# control_board.net
KiCad netlist of a schematic drawn in EAGLE
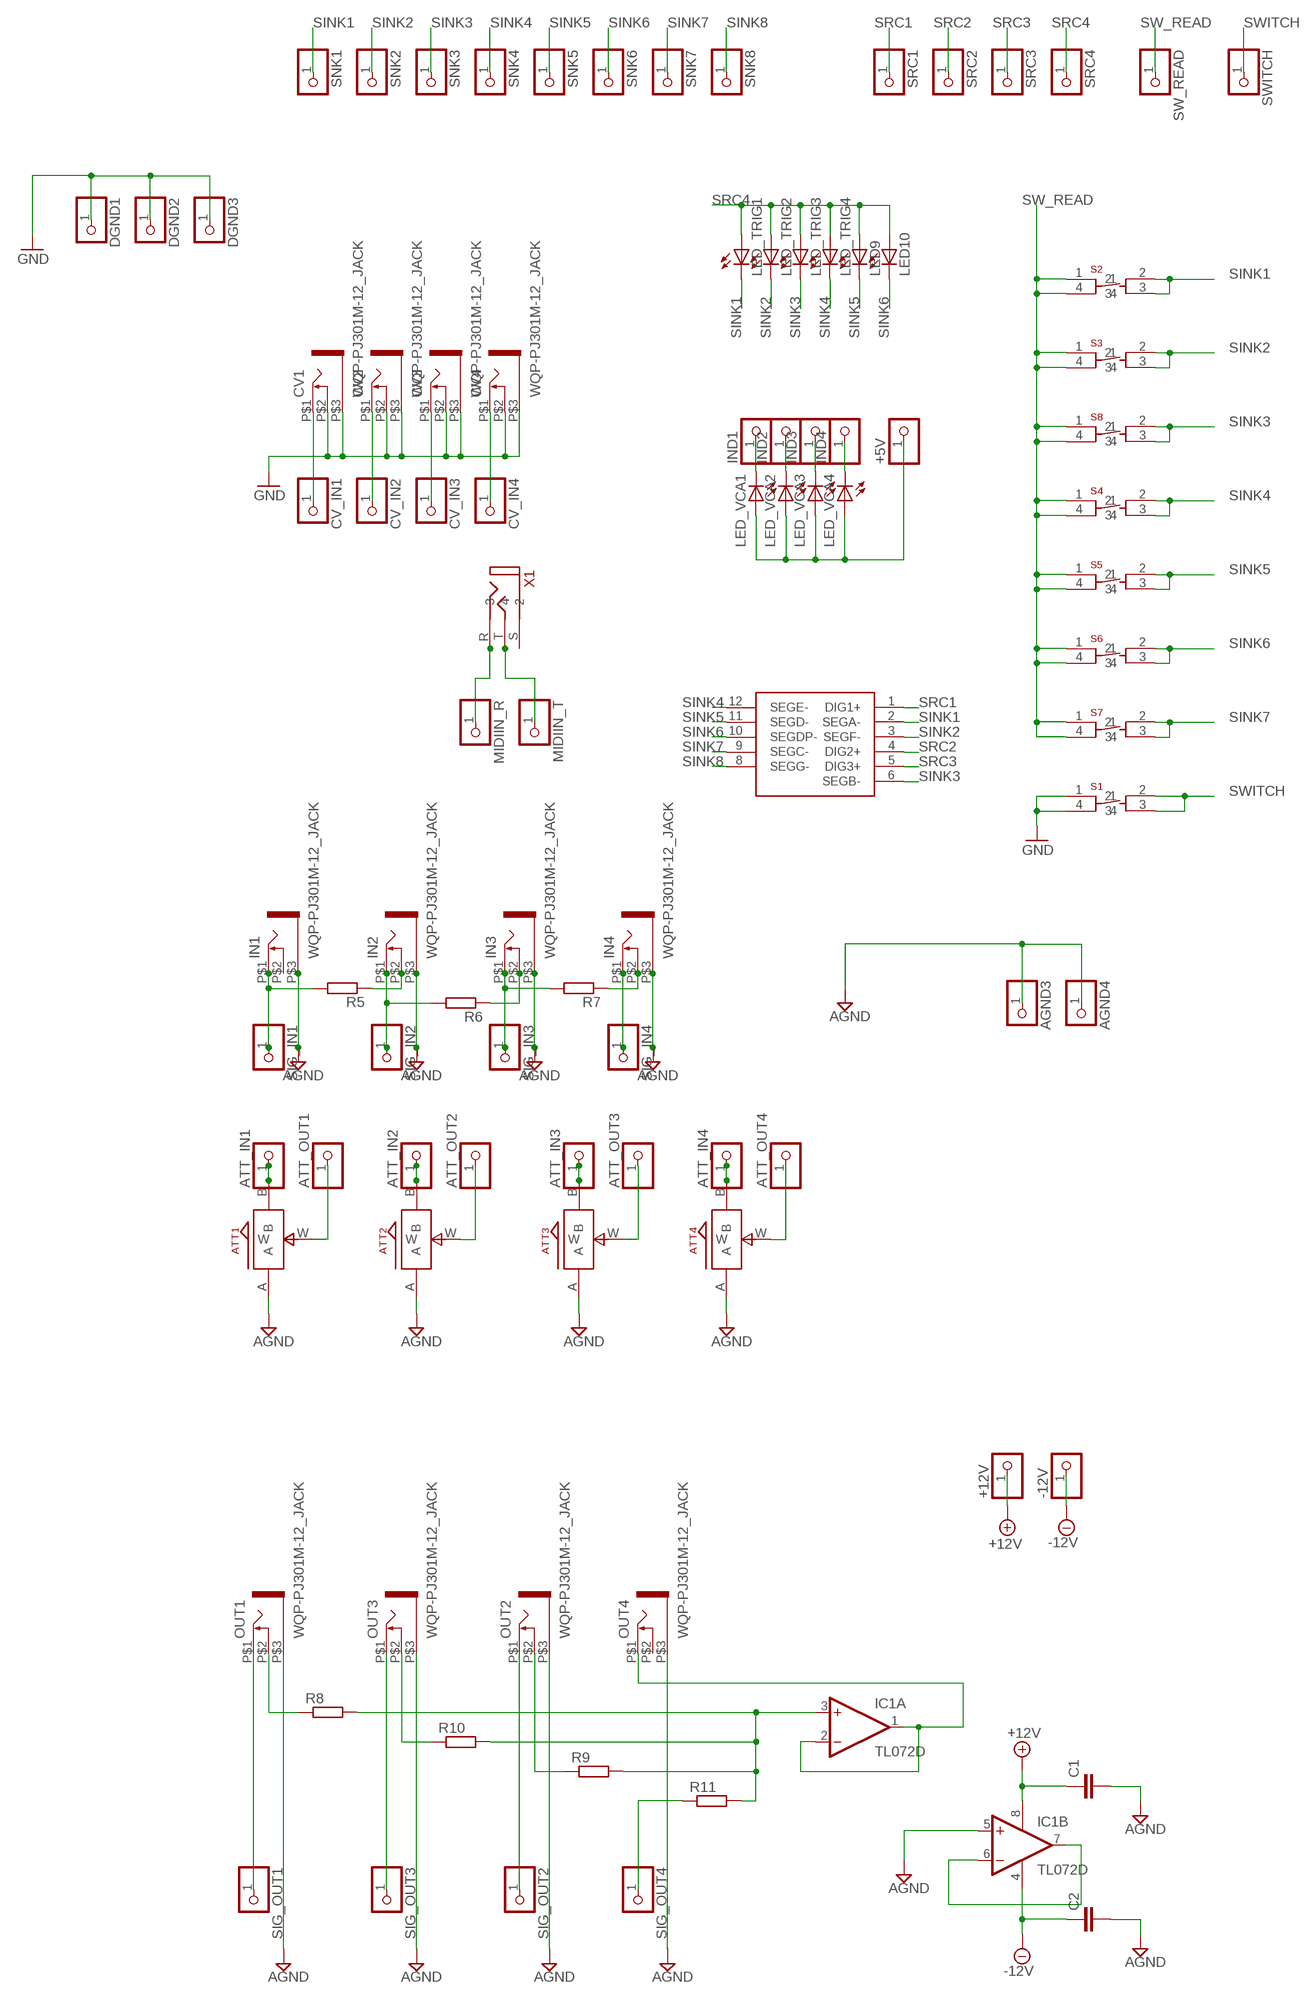
[diagram p0: schematic, sheet 1]

(export (version "E")
  (design (tool "Eeschema 10.0.6"))
  (components
    (comp (ref "+5V")
      (value "PINHD-1X1")
      (footprint "eagle-import:1X01")
      (libsource (lib "eagle-import") (part "PINHD-1X1"))
    )
    (comp (ref "+12V")
      (value "PINHD-1X1")
      (footprint "eagle-import:1X01")
      (libsource (lib "eagle-import") (part "PINHD-1X1"))
    )
    (comp (ref "-12V")
      (value "PINHD-1X1")
      (footprint "eagle-import:1X01")
      (libsource (lib "eagle-import") (part "PINHD-1X1"))
    )
    (comp (ref "AGND3")
      (value "PINHD-1X1")
      (footprint "eagle-import:1X01")
      (libsource (lib "eagle-import") (part "PINHD-1X1"))
    )
    (comp (ref "AGND4")
      (value "PINHD-1X1")
      (footprint "eagle-import:1X01")
      (libsource (lib "eagle-import") (part "PINHD-1X1"))
    )
    (comp (ref "ATT1")
      (value "ALPS_POT_SMALL")
      (footprint "eagle-import:SMALL_ALPS_POT")
      (libsource (lib "eagle-import") (part "ALPS_POT_SMALL"))
    )
    (comp (ref "ATT2")
      (value "ALPS_POT_SMALL")
      (footprint "eagle-import:SMALL_ALPS_POT")
      (libsource (lib "eagle-import") (part "ALPS_POT_SMALL"))
    )
    (comp (ref "ATT3")
      (value "ALPS_POT_SMALL")
      (footprint "eagle-import:SMALL_ALPS_POT")
      (libsource (lib "eagle-import") (part "ALPS_POT_SMALL"))
    )
    (comp (ref "ATT4")
      (value "ALPS_POT_SMALL")
      (footprint "eagle-import:SMALL_ALPS_POT")
      (libsource (lib "eagle-import") (part "ALPS_POT_SMALL"))
    )
    (comp (ref "ATT_IN1")
      (value "PINHD-1X1")
      (footprint "eagle-import:1X01")
      (libsource (lib "eagle-import") (part "PINHD-1X1"))
    )
    (comp (ref "ATT_IN2")
      (value "PINHD-1X1")
      (footprint "eagle-import:1X01")
      (libsource (lib "eagle-import") (part "PINHD-1X1"))
    )
    (comp (ref "ATT_IN3")
      (value "PINHD-1X1")
      (footprint "eagle-import:1X01")
      (libsource (lib "eagle-import") (part "PINHD-1X1"))
    )
    (comp (ref "ATT_IN4")
      (value "PINHD-1X1")
      (footprint "eagle-import:1X01")
      (libsource (lib "eagle-import") (part "PINHD-1X1"))
    )
    (comp (ref "ATT_OUT1")
      (value "PINHD-1X1")
      (footprint "eagle-import:1X01")
      (libsource (lib "eagle-import") (part "PINHD-1X1"))
    )
    (comp (ref "ATT_OUT2")
      (value "PINHD-1X1")
      (footprint "eagle-import:1X01")
      (libsource (lib "eagle-import") (part "PINHD-1X1"))
    )
    (comp (ref "ATT_OUT3")
      (value "PINHD-1X1")
      (footprint "eagle-import:1X01")
      (libsource (lib "eagle-import") (part "PINHD-1X1"))
    )
    (comp (ref "ATT_OUT4")
      (value "PINHD-1X1")
      (footprint "eagle-import:1X01")
      (libsource (lib "eagle-import") (part "PINHD-1X1"))
    )
    (comp (ref "C1")
      (value "C-EUC0805")
      (footprint "eagle-import:C0805")
      (libsource (lib "eagle-import") (part "C-EUC0805"))
    )
    (comp (ref "C2")
      (value "C-EUC0805")
      (footprint "eagle-import:C0805")
      (libsource (lib "eagle-import") (part "C-EUC0805"))
    )
    (comp (ref "CV1")
      (value "WQP-PJ301M-12_JACK")
      (footprint "eagle-import:WQP-PJ301M-12_JACK")
      (libsource (lib "eagle-import") (part "WQP-PJ301M-12_JACK"))
    )
    (comp (ref "CV2")
      (value "WQP-PJ301M-12_JACK")
      (footprint "eagle-import:WQP-PJ301M-12_JACK")
      (libsource (lib "eagle-import") (part "WQP-PJ301M-12_JACK"))
    )
    (comp (ref "CV3")
      (value "WQP-PJ301M-12_JACK")
      (footprint "eagle-import:WQP-PJ301M-12_JACK")
      (libsource (lib "eagle-import") (part "WQP-PJ301M-12_JACK"))
    )
    (comp (ref "CV4")
      (value "WQP-PJ301M-12_JACK")
      (footprint "eagle-import:WQP-PJ301M-12_JACK")
      (libsource (lib "eagle-import") (part "WQP-PJ301M-12_JACK"))
    )
    (comp (ref "CV_IN1")
      (value "PINHD-1X1")
      (footprint "eagle-import:1X01")
      (libsource (lib "eagle-import") (part "PINHD-1X1"))
    )
    (comp (ref "CV_IN2")
      (value "PINHD-1X1")
      (footprint "eagle-import:1X01")
      (libsource (lib "eagle-import") (part "PINHD-1X1"))
    )
    (comp (ref "CV_IN3")
      (value "PINHD-1X1")
      (footprint "eagle-import:1X01")
      (libsource (lib "eagle-import") (part "PINHD-1X1"))
    )
    (comp (ref "CV_IN4")
      (value "PINHD-1X1")
      (footprint "eagle-import:1X01")
      (libsource (lib "eagle-import") (part "PINHD-1X1"))
    )
    (comp (ref "DGND1")
      (value "PINHD-1X1")
      (footprint "eagle-import:1X01")
      (libsource (lib "eagle-import") (part "PINHD-1X1"))
    )
    (comp (ref "DGND2")
      (value "PINHD-1X1")
      (footprint "eagle-import:1X01")
      (libsource (lib "eagle-import") (part "PINHD-1X1"))
    )
    (comp (ref "DGND3")
      (value "PINHD-1X1")
      (footprint "eagle-import:1X01")
      (libsource (lib "eagle-import") (part "PINHD-1X1"))
    )
    (comp (ref "DISP1")
      (value "KYX2381_TRIPLE7SEG")
      (footprint "eagle-import:KYX2381_TRIPLE7SEG")
      (libsource (lib "eagle-import") (part "KYX2381_TRIPLE7SEG"))
    )
    (comp (ref "IC1")
      (value "TL072D")
      (footprint "eagle-import:SO08")
      (libsource (lib "eagle-import") (part "TL072D"))
    )
    (comp (ref "IN1")
      (value "WQP-PJ301M-12_JACK")
      (footprint "eagle-import:WQP-PJ301M-12_JACK")
      (libsource (lib "eagle-import") (part "WQP-PJ301M-12_JACK"))
    )
    (comp (ref "IN2")
      (value "WQP-PJ301M-12_JACK")
      (footprint "eagle-import:WQP-PJ301M-12_JACK")
      (libsource (lib "eagle-import") (part "WQP-PJ301M-12_JACK"))
    )
    (comp (ref "IN3")
      (value "WQP-PJ301M-12_JACK")
      (footprint "eagle-import:WQP-PJ301M-12_JACK")
      (libsource (lib "eagle-import") (part "WQP-PJ301M-12_JACK"))
    )
    (comp (ref "IN4")
      (value "WQP-PJ301M-12_JACK")
      (footprint "eagle-import:WQP-PJ301M-12_JACK")
      (libsource (lib "eagle-import") (part "WQP-PJ301M-12_JACK"))
    )
    (comp (ref "IND1")
      (value "PINHD-1X1")
      (footprint "eagle-import:1X01")
      (libsource (lib "eagle-import") (part "PINHD-1X1"))
    )
    (comp (ref "IND2")
      (value "PINHD-1X1")
      (footprint "eagle-import:1X01")
      (libsource (lib "eagle-import") (part "PINHD-1X1"))
    )
    (comp (ref "IND3")
      (value "PINHD-1X1")
      (footprint "eagle-import:1X01")
      (libsource (lib "eagle-import") (part "PINHD-1X1"))
    )
    (comp (ref "IND4")
      (value "PINHD-1X1")
      (footprint "eagle-import:1X01")
      (libsource (lib "eagle-import") (part "PINHD-1X1"))
    )
    (comp (ref "LED9")
      (value "LED3MM")
      (footprint "eagle-import:LED3MM")
      (libsource (lib "eagle-import") (part "LED3MM"))
    )
    (comp (ref "LED10")
      (value "LED3MM")
      (footprint "eagle-import:LED3MM")
      (libsource (lib "eagle-import") (part "LED3MM"))
    )
    (comp (ref "LED_TRIG1")
      (value "LED3MM")
      (footprint "eagle-import:LED3MM")
      (libsource (lib "eagle-import") (part "LED3MM"))
    )
    (comp (ref "LED_TRIG2")
      (value "LED3MM")
      (footprint "eagle-import:LED3MM")
      (libsource (lib "eagle-import") (part "LED3MM"))
    )
    (comp (ref "LED_TRIG3")
      (value "LED3MM")
      (footprint "eagle-import:LED3MM")
      (libsource (lib "eagle-import") (part "LED3MM"))
    )
    (comp (ref "LED_TRIG4")
      (value "LED3MM")
      (footprint "eagle-import:LED3MM")
      (libsource (lib "eagle-import") (part "LED3MM"))
    )
    (comp (ref "LED_VCA1")
      (value "LED3MM")
      (footprint "eagle-import:LED3MM")
      (libsource (lib "eagle-import") (part "LED3MM"))
    )
    (comp (ref "LED_VCA2")
      (value "LED3MM")
      (footprint "eagle-import:LED3MM")
      (libsource (lib "eagle-import") (part "LED3MM"))
    )
    (comp (ref "LED_VCA3")
      (value "LED3MM")
      (footprint "eagle-import:LED3MM")
      (libsource (lib "eagle-import") (part "LED3MM"))
    )
    (comp (ref "LED_VCA4")
      (value "LED3MM")
      (footprint "eagle-import:LED3MM")
      (libsource (lib "eagle-import") (part "LED3MM"))
    )
    (comp (ref "MIDIIN_R")
      (value "PINHD-1X1")
      (footprint "eagle-import:1X01")
      (libsource (lib "eagle-import") (part "PINHD-1X1"))
    )
    (comp (ref "MIDIIN_T")
      (value "PINHD-1X1")
      (footprint "eagle-import:1X01")
      (libsource (lib "eagle-import") (part "PINHD-1X1"))
    )
    (comp (ref "OUT1")
      (value "WQP-PJ301M-12_JACK")
      (footprint "eagle-import:WQP-PJ301M-12_JACK")
      (libsource (lib "eagle-import") (part "WQP-PJ301M-12_JACK"))
    )
    (comp (ref "OUT2")
      (value "WQP-PJ301M-12_JACK")
      (footprint "eagle-import:WQP-PJ301M-12_JACK")
      (libsource (lib "eagle-import") (part "WQP-PJ301M-12_JACK"))
    )
    (comp (ref "OUT3")
      (value "WQP-PJ301M-12_JACK")
      (footprint "eagle-import:WQP-PJ301M-12_JACK")
      (libsource (lib "eagle-import") (part "WQP-PJ301M-12_JACK"))
    )
    (comp (ref "OUT4")
      (value "WQP-PJ301M-12_JACK")
      (footprint "eagle-import:WQP-PJ301M-12_JACK")
      (libsource (lib "eagle-import") (part "WQP-PJ301M-12_JACK"))
    )
    (comp (ref "R5")
      (value "R-EU_R0805")
      (footprint "eagle-import:R0805")
      (libsource (lib "eagle-import") (part "R-EU_R0805"))
    )
    (comp (ref "R6")
      (value "R-EU_R0805")
      (footprint "eagle-import:R0805")
      (libsource (lib "eagle-import") (part "R-EU_R0805"))
    )
    (comp (ref "R7")
      (value "R-EU_R0805")
      (footprint "eagle-import:R0805")
      (libsource (lib "eagle-import") (part "R-EU_R0805"))
    )
    (comp (ref "R8")
      (value "R-EU_R0805")
      (footprint "eagle-import:R0805")
      (libsource (lib "eagle-import") (part "R-EU_R0805"))
    )
    (comp (ref "R9")
      (value "R-EU_R0805")
      (footprint "eagle-import:R0805")
      (libsource (lib "eagle-import") (part "R-EU_R0805"))
    )
    (comp (ref "R10")
      (value "R-EU_R0805")
      (footprint "eagle-import:R0805")
      (libsource (lib "eagle-import") (part "R-EU_R0805"))
    )
    (comp (ref "R11")
      (value "R-EU_R0805")
      (footprint "eagle-import:R0805")
      (libsource (lib "eagle-import") (part "R-EU_R0805"))
    )
    (comp (ref "S1")
      (value "6MM_TACT")
      (footprint "eagle-import:6MMTACT")
      (libsource (lib "eagle-import") (part "6MM_TACT"))
    )
    (comp (ref "S2")
      (value "6MM_TACT")
      (footprint "eagle-import:6MMTACT")
      (libsource (lib "eagle-import") (part "6MM_TACT"))
    )
    (comp (ref "S3")
      (value "6MM_TACT")
      (footprint "eagle-import:6MMTACT")
      (libsource (lib "eagle-import") (part "6MM_TACT"))
    )
    (comp (ref "S4")
      (value "6MM_TACT")
      (footprint "eagle-import:6MMTACT")
      (libsource (lib "eagle-import") (part "6MM_TACT"))
    )
    (comp (ref "S5")
      (value "6MM_TACT")
      (footprint "eagle-import:6MMTACT")
      (libsource (lib "eagle-import") (part "6MM_TACT"))
    )
    (comp (ref "S6")
      (value "6MM_TACT")
      (footprint "eagle-import:6MMTACT")
      (libsource (lib "eagle-import") (part "6MM_TACT"))
    )
    (comp (ref "S7")
      (value "6MM_TACT")
      (footprint "eagle-import:6MMTACT")
      (libsource (lib "eagle-import") (part "6MM_TACT"))
    )
    (comp (ref "S8")
      (value "6MM_TACT")
      (footprint "eagle-import:6MMTACT")
      (libsource (lib "eagle-import") (part "6MM_TACT"))
    )
    (comp (ref "SIG_IN1")
      (value "PINHD-1X1")
      (footprint "eagle-import:1X01")
      (libsource (lib "eagle-import") (part "PINHD-1X1"))
    )
    (comp (ref "SIG_IN2")
      (value "PINHD-1X1")
      (footprint "eagle-import:1X01")
      (libsource (lib "eagle-import") (part "PINHD-1X1"))
    )
    (comp (ref "SIG_IN3")
      (value "PINHD-1X1")
      (footprint "eagle-import:1X01")
      (libsource (lib "eagle-import") (part "PINHD-1X1"))
    )
    (comp (ref "SIG_IN4")
      (value "PINHD-1X1")
      (footprint "eagle-import:1X01")
      (libsource (lib "eagle-import") (part "PINHD-1X1"))
    )
    (comp (ref "SIG_OUT1")
      (value "PINHD-1X1")
      (footprint "eagle-import:1X01")
      (libsource (lib "eagle-import") (part "PINHD-1X1"))
    )
    (comp (ref "SIG_OUT2")
      (value "PINHD-1X1")
      (footprint "eagle-import:1X01")
      (libsource (lib "eagle-import") (part "PINHD-1X1"))
    )
    (comp (ref "SIG_OUT3")
      (value "PINHD-1X1")
      (footprint "eagle-import:1X01")
      (libsource (lib "eagle-import") (part "PINHD-1X1"))
    )
    (comp (ref "SIG_OUT4")
      (value "PINHD-1X1")
      (footprint "eagle-import:1X01")
      (libsource (lib "eagle-import") (part "PINHD-1X1"))
    )
    (comp (ref "SNK1")
      (value "PINHD-1X1")
      (footprint "eagle-import:1X01")
      (libsource (lib "eagle-import") (part "PINHD-1X1"))
    )
    (comp (ref "SNK2")
      (value "PINHD-1X1")
      (footprint "eagle-import:1X01")
      (libsource (lib "eagle-import") (part "PINHD-1X1"))
    )
    (comp (ref "SNK3")
      (value "PINHD-1X1")
      (footprint "eagle-import:1X01")
      (libsource (lib "eagle-import") (part "PINHD-1X1"))
    )
    (comp (ref "SNK4")
      (value "PINHD-1X1")
      (footprint "eagle-import:1X01")
      (libsource (lib "eagle-import") (part "PINHD-1X1"))
    )
    (comp (ref "SNK5")
      (value "PINHD-1X1")
      (footprint "eagle-import:1X01")
      (libsource (lib "eagle-import") (part "PINHD-1X1"))
    )
    (comp (ref "SNK6")
      (value "PINHD-1X1")
      (footprint "eagle-import:1X01")
      (libsource (lib "eagle-import") (part "PINHD-1X1"))
    )
    (comp (ref "SNK7")
      (value "PINHD-1X1")
      (footprint "eagle-import:1X01")
      (libsource (lib "eagle-import") (part "PINHD-1X1"))
    )
    (comp (ref "SNK8")
      (value "PINHD-1X1")
      (footprint "eagle-import:1X01")
      (libsource (lib "eagle-import") (part "PINHD-1X1"))
    )
    (comp (ref "SRC1")
      (value "PINHD-1X1")
      (footprint "eagle-import:1X01")
      (libsource (lib "eagle-import") (part "PINHD-1X1"))
    )
    (comp (ref "SRC2")
      (value "PINHD-1X1")
      (footprint "eagle-import:1X01")
      (libsource (lib "eagle-import") (part "PINHD-1X1"))
    )
    (comp (ref "SRC3")
      (value "PINHD-1X1")
      (footprint "eagle-import:1X01")
      (libsource (lib "eagle-import") (part "PINHD-1X1"))
    )
    (comp (ref "SRC4")
      (value "PINHD-1X1")
      (footprint "eagle-import:1X01")
      (libsource (lib "eagle-import") (part "PINHD-1X1"))
    )
    (comp (ref "SWITCH")
      (value "PINHD-1X1")
      (footprint "eagle-import:1X01")
      (libsource (lib "eagle-import") (part "PINHD-1X1"))
    )
    (comp (ref "SW_READ")
      (value "PINHD-1X1")
      (footprint "eagle-import:1X01")
      (libsource (lib "eagle-import") (part "PINHD-1X1"))
    )
    (comp (ref "X1")
      (value "VERTICAL_3_5MM_SOCKETTHONK")
      (footprint "eagle-import:PJ301CM")
      (libsource (lib "eagle-import") (part "VERTICAL_3_5MM_SOCKETTHONK"))
    )
  )
  (nets
    (net (code "1") (name "+12V") (class "Default")
      (node (ref "+12V") (pin "1") (pinfunction "1_1") (pintype "passive"))
      (node (ref "C1") (pin "1") (pinfunction "1_1") (pintype "passive"))
      (node (ref "IC1") (pin "8") (pinfunction "V+_8") (pintype "power_in"))
    )
    (net (code "2") (name "-12V") (class "Default")
      (node (ref "-12V") (pin "1") (pinfunction "1_1") (pintype "passive"))
      (node (ref "C2") (pin "1") (pinfunction "1_1") (pintype "passive"))
      (node (ref "IC1") (pin "4") (pinfunction "V-_4") (pintype "power_in"))
    )
    (net (code "3") (name "/SINK1") (class "Default")
      (node (ref "DISP1") (pin "2") (pinfunction "SEGA-_2") (pintype "bidirectional"))
      (node (ref "LED_TRIG1") (pin "K") (pinfunction "C_K") (pintype "passive"))
      (node (ref "S2") (pin "2") (pinfunction "2_2") (pintype "bidirectional"))
      (node (ref "S2") (pin "3") (pinfunction "3_3") (pintype "bidirectional"))
      (node (ref "SNK1") (pin "1") (pinfunction "1_1") (pintype "passive"))
    )
    (net (code "4") (name "/SINK2") (class "Default")
      (node (ref "DISP1") (pin "3") (pinfunction "SEGF-_3") (pintype "bidirectional"))
      (node (ref "LED_TRIG2") (pin "K") (pinfunction "C_K") (pintype "passive"))
      (node (ref "S3") (pin "2") (pinfunction "2_2") (pintype "bidirectional"))
      (node (ref "S3") (pin "3") (pinfunction "3_3") (pintype "bidirectional"))
      (node (ref "SNK2") (pin "1") (pinfunction "1_1") (pintype "passive"))
    )
    (net (code "5") (name "/SINK3") (class "Default")
      (node (ref "DISP1") (pin "6") (pinfunction "SEGB-_6") (pintype "bidirectional"))
      (node (ref "LED_TRIG3") (pin "K") (pinfunction "C_K") (pintype "passive"))
      (node (ref "S8") (pin "2") (pinfunction "2_2") (pintype "bidirectional"))
      (node (ref "S8") (pin "3") (pinfunction "3_3") (pintype "bidirectional"))
      (node (ref "SNK3") (pin "1") (pinfunction "1_1") (pintype "passive"))
    )
    (net (code "6") (name "/SINK4") (class "Default")
      (node (ref "DISP1") (pin "12") (pinfunction "SEGE-_12") (pintype "bidirectional"))
      (node (ref "LED_TRIG4") (pin "K") (pinfunction "C_K") (pintype "passive"))
      (node (ref "S4") (pin "2") (pinfunction "2_2") (pintype "bidirectional"))
      (node (ref "S4") (pin "3") (pinfunction "3_3") (pintype "bidirectional"))
      (node (ref "SNK4") (pin "1") (pinfunction "1_1") (pintype "passive"))
    )
    (net (code "7") (name "/SINK5") (class "Default")
      (node (ref "DISP1") (pin "11") (pinfunction "SEGD-_11") (pintype "bidirectional"))
      (node (ref "LED9") (pin "K") (pinfunction "C_K") (pintype "passive"))
      (node (ref "S5") (pin "2") (pinfunction "2_2") (pintype "bidirectional"))
      (node (ref "S5") (pin "3") (pinfunction "3_3") (pintype "bidirectional"))
      (node (ref "SNK5") (pin "1") (pinfunction "1_1") (pintype "passive"))
    )
    (net (code "8") (name "/SINK6") (class "Default")
      (node (ref "DISP1") (pin "10") (pinfunction "SEGDP-_10") (pintype "bidirectional"))
      (node (ref "LED10") (pin "K") (pinfunction "C_K") (pintype "passive"))
      (node (ref "S6") (pin "2") (pinfunction "2_2") (pintype "bidirectional"))
      (node (ref "S6") (pin "3") (pinfunction "3_3") (pintype "bidirectional"))
      (node (ref "SNK6") (pin "1") (pinfunction "1_1") (pintype "passive"))
    )
    (net (code "9") (name "/SINK7") (class "Default")
      (node (ref "DISP1") (pin "9") (pinfunction "SEGC-_9") (pintype "bidirectional"))
      (node (ref "S7") (pin "2") (pinfunction "2_2") (pintype "bidirectional"))
      (node (ref "S7") (pin "3") (pinfunction "3_3") (pintype "bidirectional"))
      (node (ref "SNK7") (pin "1") (pinfunction "1_1") (pintype "passive"))
    )
    (net (code "10") (name "/SINK8") (class "Default")
      (node (ref "DISP1") (pin "8") (pinfunction "SEGG-_8") (pintype "bidirectional"))
      (node (ref "SNK8") (pin "1") (pinfunction "1_1") (pintype "passive"))
    )
    (net (code "11") (name "/SRC1") (class "Default")
      (node (ref "DISP1") (pin "1") (pinfunction "DIG1+_1") (pintype "bidirectional"))
      (node (ref "SRC1") (pin "1") (pinfunction "1_1") (pintype "passive"))
    )
    (net (code "12") (name "/SRC2") (class "Default")
      (node (ref "DISP1") (pin "4") (pinfunction "DIG2+_4") (pintype "bidirectional"))
      (node (ref "SRC2") (pin "1") (pinfunction "1_1") (pintype "passive"))
    )
    (net (code "13") (name "/SRC3") (class "Default")
      (node (ref "DISP1") (pin "5") (pinfunction "DIG3+_5") (pintype "bidirectional"))
      (node (ref "SRC3") (pin "1") (pinfunction "1_1") (pintype "passive"))
    )
    (net (code "14") (name "/SRC4") (class "Default")
      (node (ref "LED10") (pin "A") (pinfunction "A_A") (pintype "passive"))
      (node (ref "LED9") (pin "A") (pinfunction "A_A") (pintype "passive"))
      (node (ref "LED_TRIG1") (pin "A") (pinfunction "A_A") (pintype "passive"))
      (node (ref "LED_TRIG2") (pin "A") (pinfunction "A_A") (pintype "passive"))
      (node (ref "LED_TRIG3") (pin "A") (pinfunction "A_A") (pintype "passive"))
      (node (ref "LED_TRIG4") (pin "A") (pinfunction "A_A") (pintype "passive"))
      (node (ref "SRC4") (pin "1") (pinfunction "1_1") (pintype "passive"))
    )
    (net (code "15") (name "/SWITCH") (class "Default")
      (node (ref "S1") (pin "2") (pinfunction "2_2") (pintype "bidirectional"))
      (node (ref "S1") (pin "3") (pinfunction "3_3") (pintype "bidirectional"))
      (node (ref "SWITCH") (pin "1") (pinfunction "1_1") (pintype "passive"))
    )
    (net (code "16") (name "/SW_READ") (class "Default")
      (node (ref "S2") (pin "1") (pinfunction "1_1") (pintype "bidirectional"))
      (node (ref "S2") (pin "4") (pinfunction "4_4") (pintype "bidirectional"))
      (node (ref "S3") (pin "1") (pinfunction "1_1") (pintype "bidirectional"))
      (node (ref "S3") (pin "4") (pinfunction "4_4") (pintype "bidirectional"))
      (node (ref "S4") (pin "1") (pinfunction "1_1") (pintype "bidirectional"))
      (node (ref "S4") (pin "4") (pinfunction "4_4") (pintype "bidirectional"))
      (node (ref "S5") (pin "1") (pinfunction "1_1") (pintype "bidirectional"))
      (node (ref "S5") (pin "4") (pinfunction "4_4") (pintype "bidirectional"))
      (node (ref "S6") (pin "1") (pinfunction "1_1") (pintype "bidirectional"))
      (node (ref "S6") (pin "4") (pinfunction "4_4") (pintype "bidirectional"))
      (node (ref "S7") (pin "1") (pinfunction "1_1") (pintype "bidirectional"))
      (node (ref "S7") (pin "4") (pinfunction "4_4") (pintype "bidirectional"))
      (node (ref "S8") (pin "1") (pinfunction "1_1") (pintype "bidirectional"))
      (node (ref "S8") (pin "4") (pinfunction "4_4") (pintype "bidirectional"))
      (node (ref "SW_READ") (pin "1") (pinfunction "1_1") (pintype "passive"))
    )
    (net (code "17") (name "AGND") (class "Default")
      (node (ref "AGND3") (pin "1") (pinfunction "1_1") (pintype "passive"))
      (node (ref "AGND4") (pin "1") (pinfunction "1_1") (pintype "passive"))
      (node (ref "ATT1") (pin "A") (pinfunction "A_A") (pintype "bidirectional"))
      (node (ref "ATT2") (pin "A") (pinfunction "A_A") (pintype "bidirectional"))
      (node (ref "ATT3") (pin "A") (pinfunction "A_A") (pintype "bidirectional"))
      (node (ref "ATT4") (pin "A") (pinfunction "A_A") (pintype "bidirectional"))
      (node (ref "C1") (pin "2") (pinfunction "2_2") (pintype "passive"))
      (node (ref "C2") (pin "2") (pinfunction "2_2") (pintype "passive"))
      (node (ref "IC1") (pin "5") (pinfunction "+IN_5") (pintype "input"))
      (node (ref "IN1") (pin "P$3") (pinfunction "1_P$3") (pintype "passive"))
      (node (ref "IN2") (pin "P$3") (pinfunction "1_P$3") (pintype "passive"))
      (node (ref "IN3") (pin "P$3") (pinfunction "1_P$3") (pintype "passive"))
      (node (ref "IN4") (pin "P$3") (pinfunction "1_P$3") (pintype "passive"))
      (node (ref "OUT1") (pin "P$3") (pinfunction "1_P$3") (pintype "passive"))
      (node (ref "OUT2") (pin "P$3") (pinfunction "1_P$3") (pintype "passive"))
      (node (ref "OUT3") (pin "P$3") (pinfunction "1_P$3") (pintype "passive"))
      (node (ref "OUT4") (pin "P$3") (pinfunction "1_P$3") (pintype "passive"))
    )
    (net (code "18") (name "GND") (class "Default")
      (node (ref "CV1") (pin "P$2") (pinfunction "3_P$2") (pintype "passive"))
      (node (ref "CV1") (pin "P$3") (pinfunction "1_P$3") (pintype "passive"))
      (node (ref "CV2") (pin "P$2") (pinfunction "3_P$2") (pintype "passive"))
      (node (ref "CV2") (pin "P$3") (pinfunction "1_P$3") (pintype "passive"))
      (node (ref "CV3") (pin "P$2") (pinfunction "3_P$2") (pintype "passive"))
      (node (ref "CV3") (pin "P$3") (pinfunction "1_P$3") (pintype "passive"))
      (node (ref "CV4") (pin "P$2") (pinfunction "3_P$2") (pintype "passive"))
      (node (ref "CV4") (pin "P$3") (pinfunction "1_P$3") (pintype "passive"))
      (node (ref "DGND1") (pin "1") (pinfunction "1_1") (pintype "passive"))
      (node (ref "DGND2") (pin "1") (pinfunction "1_1") (pintype "passive"))
      (node (ref "DGND3") (pin "1") (pinfunction "1_1") (pintype "passive"))
      (node (ref "S1") (pin "1") (pinfunction "1_1") (pintype "bidirectional"))
      (node (ref "S1") (pin "4") (pinfunction "4_4") (pintype "bidirectional"))
    )
    (net (code "19") (name "Net-(+5V-Pad1)") (class "Default")
      (node (ref "+5V") (pin "1") (pinfunction "1_1") (pintype "passive"))
      (node (ref "LED_VCA1") (pin "A") (pinfunction "A_A") (pintype "passive"))
      (node (ref "LED_VCA2") (pin "A") (pinfunction "A_A") (pintype "passive"))
      (node (ref "LED_VCA3") (pin "A") (pinfunction "A_A") (pintype "passive"))
      (node (ref "LED_VCA4") (pin "A") (pinfunction "A_A") (pintype "passive"))
    )
    (net (code "20") (name "Net-(ATT1-PadB)") (class "Default")
      (node (ref "ATT1") (pin "B") (pinfunction "B_B") (pintype "bidirectional"))
      (node (ref "ATT_IN1") (pin "1") (pinfunction "1_1") (pintype "passive"))
    )
    (net (code "21") (name "Net-(ATT1-PadW)") (class "Default")
      (node (ref "ATT1") (pin "W") (pinfunction "W_W") (pintype "bidirectional"))
      (node (ref "ATT_OUT1") (pin "1") (pinfunction "1_1") (pintype "passive"))
    )
    (net (code "22") (name "Net-(ATT2-PadB)") (class "Default")
      (node (ref "ATT2") (pin "B") (pinfunction "B_B") (pintype "bidirectional"))
      (node (ref "ATT_IN2") (pin "1") (pinfunction "1_1") (pintype "passive"))
    )
    (net (code "23") (name "Net-(ATT2-PadW)") (class "Default")
      (node (ref "ATT2") (pin "W") (pinfunction "W_W") (pintype "bidirectional"))
      (node (ref "ATT_OUT2") (pin "1") (pinfunction "1_1") (pintype "passive"))
    )
    (net (code "24") (name "Net-(ATT3-PadB)") (class "Default")
      (node (ref "ATT3") (pin "B") (pinfunction "B_B") (pintype "bidirectional"))
      (node (ref "ATT_IN3") (pin "1") (pinfunction "1_1") (pintype "passive"))
    )
    (net (code "25") (name "Net-(ATT3-PadW)") (class "Default")
      (node (ref "ATT3") (pin "W") (pinfunction "W_W") (pintype "bidirectional"))
      (node (ref "ATT_OUT3") (pin "1") (pinfunction "1_1") (pintype "passive"))
    )
    (net (code "26") (name "Net-(ATT4-PadB)") (class "Default")
      (node (ref "ATT4") (pin "B") (pinfunction "B_B") (pintype "bidirectional"))
      (node (ref "ATT_IN4") (pin "1") (pinfunction "1_1") (pintype "passive"))
    )
    (net (code "27") (name "Net-(ATT4-PadW)") (class "Default")
      (node (ref "ATT4") (pin "W") (pinfunction "W_W") (pintype "bidirectional"))
      (node (ref "ATT_OUT4") (pin "1") (pinfunction "1_1") (pintype "passive"))
    )
    (net (code "28") (name "Net-(CV1-2)") (class "Default")
      (node (ref "CV1") (pin "P$1") (pinfunction "2_P$1") (pintype "passive"))
      (node (ref "CV_IN1") (pin "1") (pinfunction "1_1") (pintype "passive"))
    )
    (net (code "29") (name "Net-(CV2-2)") (class "Default")
      (node (ref "CV2") (pin "P$1") (pinfunction "2_P$1") (pintype "passive"))
      (node (ref "CV_IN2") (pin "1") (pinfunction "1_1") (pintype "passive"))
    )
    (net (code "30") (name "Net-(CV3-2)") (class "Default")
      (node (ref "CV3") (pin "P$1") (pinfunction "2_P$1") (pintype "passive"))
      (node (ref "CV_IN3") (pin "1") (pinfunction "1_1") (pintype "passive"))
    )
    (net (code "31") (name "Net-(CV4-2)") (class "Default")
      (node (ref "CV4") (pin "P$1") (pinfunction "2_P$1") (pintype "passive"))
      (node (ref "CV_IN4") (pin "1") (pinfunction "1_1") (pintype "passive"))
    )
    (net (code "32") (name "Net-(IC1A-+IN)") (class "Default")
      (node (ref "IC1") (pin "3") (pinfunction "+IN_3") (pintype "input"))
      (node (ref "R10") (pin "2") (pinfunction "2_2") (pintype "passive"))
      (node (ref "R11") (pin "2") (pinfunction "2_2") (pintype "passive"))
      (node (ref "R8") (pin "2") (pinfunction "2_2") (pintype "passive"))
      (node (ref "R9") (pin "2") (pinfunction "2_2") (pintype "passive"))
    )
    (net (code "33") (name "Net-(IC1A--IN)") (class "Default")
      (node (ref "IC1") (pin "1") (pinfunction "OUT_1") (pintype "output"))
      (node (ref "IC1") (pin "2") (pinfunction "-IN_2") (pintype "input"))
      (node (ref "OUT4") (pin "P$1") (pinfunction "2_P$1") (pintype "passive"))
    )
    (net (code "34") (name "Net-(IC1B--IN)") (class "Default")
      (node (ref "IC1") (pin "6") (pinfunction "-IN_6") (pintype "input"))
      (node (ref "IC1") (pin "7") (pinfunction "OUT_7") (pintype "output"))
    )
    (net (code "35") (name "Net-(IN1-2)") (class "Default")
      (node (ref "IN1") (pin "P$1") (pinfunction "2_P$1") (pintype "passive"))
      (node (ref "R5") (pin "2") (pinfunction "2_2") (pintype "passive"))
      (node (ref "SIG_IN1") (pin "1") (pinfunction "1_1") (pintype "passive"))
    )
    (net (code "36") (name "Net-(IN2-2)") (class "Default")
      (node (ref "IN2") (pin "P$1") (pinfunction "2_P$1") (pintype "passive"))
      (node (ref "R6") (pin "2") (pinfunction "2_2") (pintype "passive"))
      (node (ref "SIG_IN2") (pin "1") (pinfunction "1_1") (pintype "passive"))
    )
    (net (code "37") (name "Net-(IN2-3)") (class "Default")
      (node (ref "IN2") (pin "P$2") (pinfunction "3_P$2") (pintype "passive"))
      (node (ref "R5") (pin "1") (pinfunction "1_1") (pintype "passive"))
    )
    (net (code "38") (name "Net-(IN3-2)") (class "Default")
      (node (ref "IN3") (pin "P$1") (pinfunction "2_P$1") (pintype "passive"))
      (node (ref "R7") (pin "2") (pinfunction "2_2") (pintype "passive"))
      (node (ref "SIG_IN3") (pin "1") (pinfunction "1_1") (pintype "passive"))
    )
    (net (code "39") (name "Net-(IN3-3)") (class "Default")
      (node (ref "IN3") (pin "P$2") (pinfunction "3_P$2") (pintype "passive"))
      (node (ref "R6") (pin "1") (pinfunction "1_1") (pintype "passive"))
    )
    (net (code "40") (name "Net-(IN4-2)") (class "Default")
      (node (ref "IN4") (pin "P$1") (pinfunction "2_P$1") (pintype "passive"))
      (node (ref "SIG_IN4") (pin "1") (pinfunction "1_1") (pintype "passive"))
    )
    (net (code "41") (name "Net-(IN4-3)") (class "Default")
      (node (ref "IN4") (pin "P$2") (pinfunction "3_P$2") (pintype "passive"))
      (node (ref "R7") (pin "1") (pinfunction "1_1") (pintype "passive"))
    )
    (net (code "42") (name "Net-(LED_VCA1-C)") (class "Default")
      (node (ref "IND1") (pin "1") (pinfunction "1_1") (pintype "passive"))
      (node (ref "LED_VCA1") (pin "K") (pinfunction "C_K") (pintype "passive"))
    )
    (net (code "43") (name "Net-(LED_VCA2-C)") (class "Default")
      (node (ref "IND2") (pin "1") (pinfunction "1_1") (pintype "passive"))
      (node (ref "LED_VCA2") (pin "K") (pinfunction "C_K") (pintype "passive"))
    )
    (net (code "44") (name "Net-(LED_VCA3-C)") (class "Default")
      (node (ref "IND3") (pin "1") (pinfunction "1_1") (pintype "passive"))
      (node (ref "LED_VCA3") (pin "K") (pinfunction "C_K") (pintype "passive"))
    )
    (net (code "45") (name "Net-(LED_VCA4-C)") (class "Default")
      (node (ref "IND4") (pin "1") (pinfunction "1_1") (pintype "passive"))
      (node (ref "LED_VCA4") (pin "K") (pinfunction "C_K") (pintype "passive"))
    )
    (net (code "46") (name "Net-(OUT1-2)") (class "Default")
      (node (ref "OUT1") (pin "P$1") (pinfunction "2_P$1") (pintype "passive"))
      (node (ref "SIG_OUT1") (pin "1") (pinfunction "1_1") (pintype "passive"))
    )
    (net (code "47") (name "Net-(OUT1-3)") (class "Default")
      (node (ref "OUT1") (pin "P$2") (pinfunction "3_P$2") (pintype "passive"))
      (node (ref "R8") (pin "1") (pinfunction "1_1") (pintype "passive"))
    )
    (net (code "48") (name "Net-(OUT2-2)") (class "Default")
      (node (ref "OUT2") (pin "P$1") (pinfunction "2_P$1") (pintype "passive"))
      (node (ref "SIG_OUT2") (pin "1") (pinfunction "1_1") (pintype "passive"))
    )
    (net (code "49") (name "Net-(OUT2-3)") (class "Default")
      (node (ref "OUT2") (pin "P$2") (pinfunction "3_P$2") (pintype "passive"))
      (node (ref "R9") (pin "1") (pinfunction "1_1") (pintype "passive"))
    )
    (net (code "50") (name "Net-(OUT3-2)") (class "Default")
      (node (ref "OUT3") (pin "P$1") (pinfunction "2_P$1") (pintype "passive"))
      (node (ref "SIG_OUT3") (pin "1") (pinfunction "1_1") (pintype "passive"))
    )
    (net (code "51") (name "Net-(OUT3-3)") (class "Default")
      (node (ref "OUT3") (pin "P$2") (pinfunction "3_P$2") (pintype "passive"))
      (node (ref "R10") (pin "1") (pinfunction "1_1") (pintype "passive"))
    )
    (net (code "52") (name "Net-(R11-Pad1)") (class "Default")
      (node (ref "R11") (pin "1") (pinfunction "1_1") (pintype "passive"))
      (node (ref "SIG_OUT4") (pin "1") (pinfunction "1_1") (pintype "passive"))
    )
    (net (code "53") (name "Net-(X1-3)") (class "Default")
      (node (ref "MIDIIN_R") (pin "1") (pinfunction "1_1") (pintype "passive"))
      (node (ref "X1") (pin "R") (pinfunction "3_R") (pintype "bidirectional"))
    )
    (net (code "54") (name "Net-(X1-4)") (class "Default")
      (node (ref "MIDIIN_T") (pin "1") (pinfunction "1_1") (pintype "passive"))
      (node (ref "X1") (pin "T") (pinfunction "4_T") (pintype "bidirectional"))
    )
    (net (code "55") (name "unconnected-(IN1-3-PadP$2)") (class "Default")
      (node (ref "IN1") (pin "P$2") (pinfunction "3_P$2") (pintype "passive"))
    )
    (net (code "56") (name "unconnected-(OUT4-3-PadP$2)") (class "Default")
      (node (ref "OUT4") (pin "P$2") (pinfunction "3_P$2") (pintype "passive"))
    )
    (net (code "57") (name "unconnected-(X1-2-PadS)") (class "Default")
      (node (ref "X1") (pin "S") (pinfunction "2_S") (pintype "bidirectional"))
    )
  )
)
